# PWM.net
KiCad netlist of a schematic drawn in Altium Designer
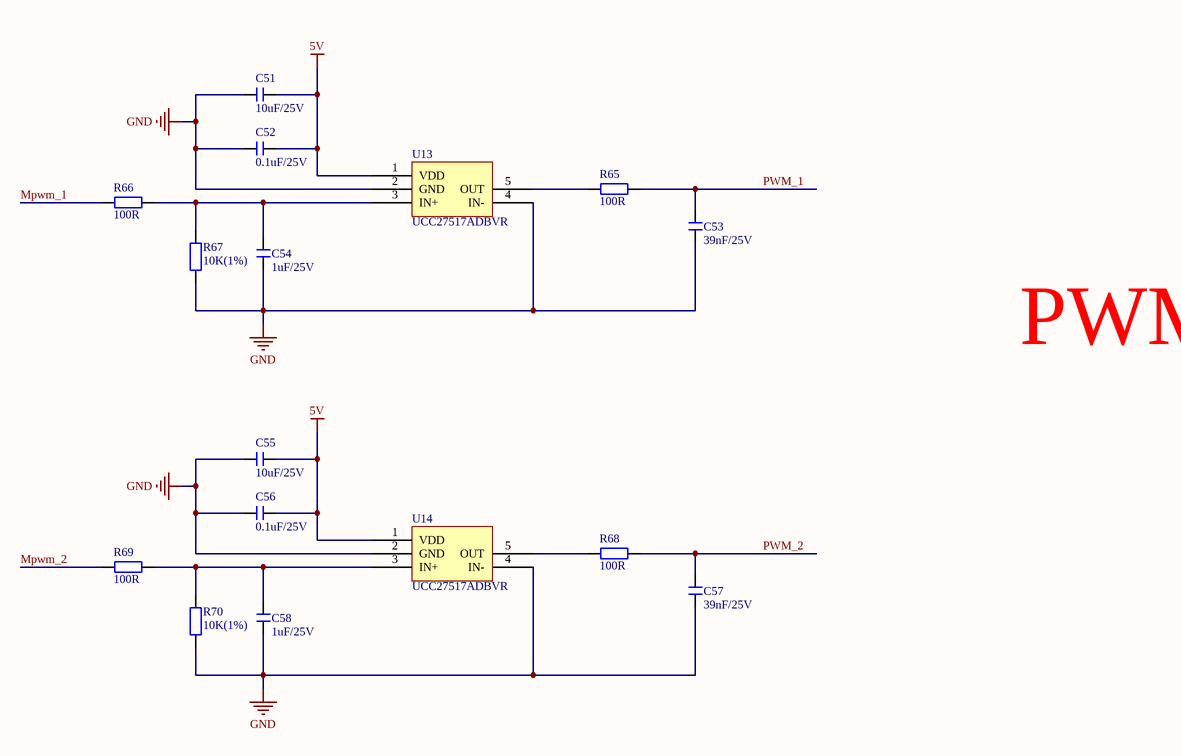
[diagram p0: PWM.SchDoc]

(export (version "E")
  (design (tool "Eeschema 10.0.6"))
  (components
    (comp (ref "C51")
      (value "10uF/25V")
      (footprint "C 0603_L")
      (description "无极性贴片电容")
      (fields (field (name "版权归属") "源创客"))
      (libsource (lib "电阻-电容-电感") (part "C"))
    )
    (comp (ref "C52")
      (value "0.1uF/25V")
      (footprint "C 0603_L")
      (description "无极性贴片电容")
      (fields (field (name "版权归属") "源创客"))
      (libsource (lib "电阻-电容-电感") (part "C"))
    )
    (comp (ref "C53")
      (value "39nF/25V")
      (footprint "C 0603_L")
      (description "无极性贴片电容")
      (fields (field (name "版权归属") "源创客"))
      (libsource (lib "电阻-电容-电感") (part "C"))
    )
    (comp (ref "C54")
      (value "1uF/25V")
      (footprint "C 0603_L")
      (description "无极性贴片电容")
      (fields (field (name "版权归属") "源创客"))
      (libsource (lib "电阻-电容-电感") (part "C"))
    )
    (comp (ref "C55")
      (value "10uF/25V")
      (footprint "C 0603_L")
      (description "无极性贴片电容")
      (fields (field (name "版权归属") "源创客"))
      (libsource (lib "电阻-电容-电感") (part "C"))
    )
    (comp (ref "C56")
      (value "0.1uF/25V")
      (footprint "C 0603_L")
      (description "无极性贴片电容")
      (fields (field (name "版权归属") "源创客"))
      (libsource (lib "电阻-电容-电感") (part "C"))
    )
    (comp (ref "C57")
      (value "39nF/25V")
      (footprint "C 0603_L")
      (description "无极性贴片电容")
      (fields (field (name "版权归属") "源创客"))
      (libsource (lib "电阻-电容-电感") (part "C"))
    )
    (comp (ref "C58")
      (value "1uF/25V")
      (footprint "C 0603_L")
      (description "无极性贴片电容")
      (fields (field (name "版权归属") "源创客"))
      (libsource (lib "电阻-电容-电感") (part "C"))
    )
    (comp (ref "R65")
      (value "100R")
      (footprint "R 0603_L")
      (description "贴片电阻")
      (fields (field (name "版权归属") "源创客"))
      (libsource (lib "电阻-电容-电感") (part "R"))
    )
    (comp (ref "R66")
      (value "100R")
      (footprint "R 0603_L")
      (description "贴片电阻")
      (fields (field (name "版权归属") "源创客"))
      (libsource (lib "电阻-电容-电感") (part "R"))
    )
    (comp (ref "R67")
      (value "10K(1%)")
      (footprint "R 0603_L")
      (description "贴片电阻")
      (fields (field (name "版权归属") "源创客"))
      (libsource (lib "电阻-电容-电感") (part "R"))
    )
    (comp (ref "R68")
      (value "100R")
      (footprint "R 0603_L")
      (description "贴片电阻")
      (fields (field (name "版权归属") "源创客"))
      (libsource (lib "电阻-电容-电感") (part "R"))
    )
    (comp (ref "R69")
      (value "100R")
      (footprint "R 0603_L")
      (description "贴片电阻")
      (fields (field (name "版权归属") "源创客"))
      (libsource (lib "电阻-电容-电感") (part "R"))
    )
    (comp (ref "R70")
      (value "10K(1%)")
      (footprint "R 0603_L")
      (description "贴片电阻")
      (fields (field (name "版权归属") "源创客"))
      (libsource (lib "电阻-电容-电感") (part "R"))
    )
    (comp (ref "U13")
      (value "UCC27517ADBVR")
      (footprint "SOT23-5N")
      (libsource (lib "MICB") (part "UCC27517ADBVR"))
    )
    (comp (ref "U14")
      (value "UCC27517ADBVR")
      (footprint "SOT23-5N")
      (libsource (lib "MICB") (part "UCC27517ADBVR"))
    )
  )
  (nets
    (net (code "1") (name "/Mpwm_1") (class "Default")
      (node (ref "R66") (pin "2") (pinfunction "2_2") (pintype "passive"))
    )
    (net (code "2") (name "/Mpwm_2") (class "Default")
      (node (ref "R69") (pin "2") (pinfunction "2_2") (pintype "passive"))
    )
    (net (code "3") (name "/PWM_1") (class "Default")
      (node (ref "C53") (pin "2") (pinfunction "2_2") (pintype "passive"))
      (node (ref "R65") (pin "1") (pinfunction "1_1") (pintype "passive"))
    )
    (net (code "4") (name "/PWM_2") (class "Default")
      (node (ref "C57") (pin "2") (pinfunction "2_2") (pintype "passive"))
      (node (ref "R68") (pin "1") (pinfunction "1_1") (pintype "passive"))
    )
    (net (code "5") (name "5V") (class "Default")
      (node (ref "C51") (pin "1") (pinfunction "1_1") (pintype "passive"))
      (node (ref "C52") (pin "1") (pinfunction "1_1") (pintype "passive"))
      (node (ref "C55") (pin "1") (pinfunction "1_1") (pintype "passive"))
      (node (ref "C56") (pin "1") (pinfunction "1_1") (pintype "passive"))
      (node (ref "U13") (pin "1") (pinfunction "VDD_1") (pintype "passive"))
      (node (ref "U14") (pin "1") (pinfunction "VDD_1") (pintype "passive"))
    )
    (net (code "6") (name "GND") (class "Default")
      (node (ref "C51") (pin "2") (pinfunction "2_2") (pintype "passive"))
      (node (ref "C52") (pin "2") (pinfunction "2_2") (pintype "passive"))
      (node (ref "C53") (pin "1") (pinfunction "1_1") (pintype "passive"))
      (node (ref "C54") (pin "1") (pinfunction "1_1") (pintype "passive"))
      (node (ref "C55") (pin "2") (pinfunction "2_2") (pintype "passive"))
      (node (ref "C56") (pin "2") (pinfunction "2_2") (pintype "passive"))
      (node (ref "C57") (pin "1") (pinfunction "1_1") (pintype "passive"))
      (node (ref "C58") (pin "1") (pinfunction "1_1") (pintype "passive"))
      (node (ref "R67") (pin "2") (pinfunction "2_2") (pintype "passive"))
      (node (ref "R70") (pin "2") (pinfunction "2_2") (pintype "passive"))
      (node (ref "U13") (pin "2") (pinfunction "GND_2") (pintype "passive"))
      (node (ref "U13") (pin "4") (pinfunction "IN-_4") (pintype "passive"))
      (node (ref "U14") (pin "2") (pinfunction "GND_2") (pintype "passive"))
      (node (ref "U14") (pin "4") (pinfunction "IN-_4") (pintype "passive"))
    )
    (net (code "7") (name "Net-(U13-IN+)") (class "Default")
      (node (ref "C54") (pin "2") (pinfunction "2_2") (pintype "passive"))
      (node (ref "R66") (pin "1") (pinfunction "1_1") (pintype "passive"))
      (node (ref "R67") (pin "1") (pinfunction "1_1") (pintype "passive"))
      (node (ref "U13") (pin "3") (pinfunction "IN+_3") (pintype "passive"))
    )
    (net (code "8") (name "Net-(U13-OUT)") (class "Default")
      (node (ref "R65") (pin "2") (pinfunction "2_2") (pintype "passive"))
      (node (ref "U13") (pin "5") (pinfunction "OUT_5") (pintype "passive"))
    )
    (net (code "9") (name "Net-(U14-IN+)") (class "Default")
      (node (ref "C58") (pin "2") (pinfunction "2_2") (pintype "passive"))
      (node (ref "R69") (pin "1") (pinfunction "1_1") (pintype "passive"))
      (node (ref "R70") (pin "1") (pinfunction "1_1") (pintype "passive"))
      (node (ref "U14") (pin "3") (pinfunction "IN+_3") (pintype "passive"))
    )
    (net (code "10") (name "Net-(U14-OUT)") (class "Default")
      (node (ref "R68") (pin "2") (pinfunction "2_2") (pintype "passive"))
      (node (ref "U14") (pin "5") (pinfunction "OUT_5") (pintype "passive"))
    )
  )
)
